# toastershield.net
KiCad netlist of a schematic drawn in EAGLE
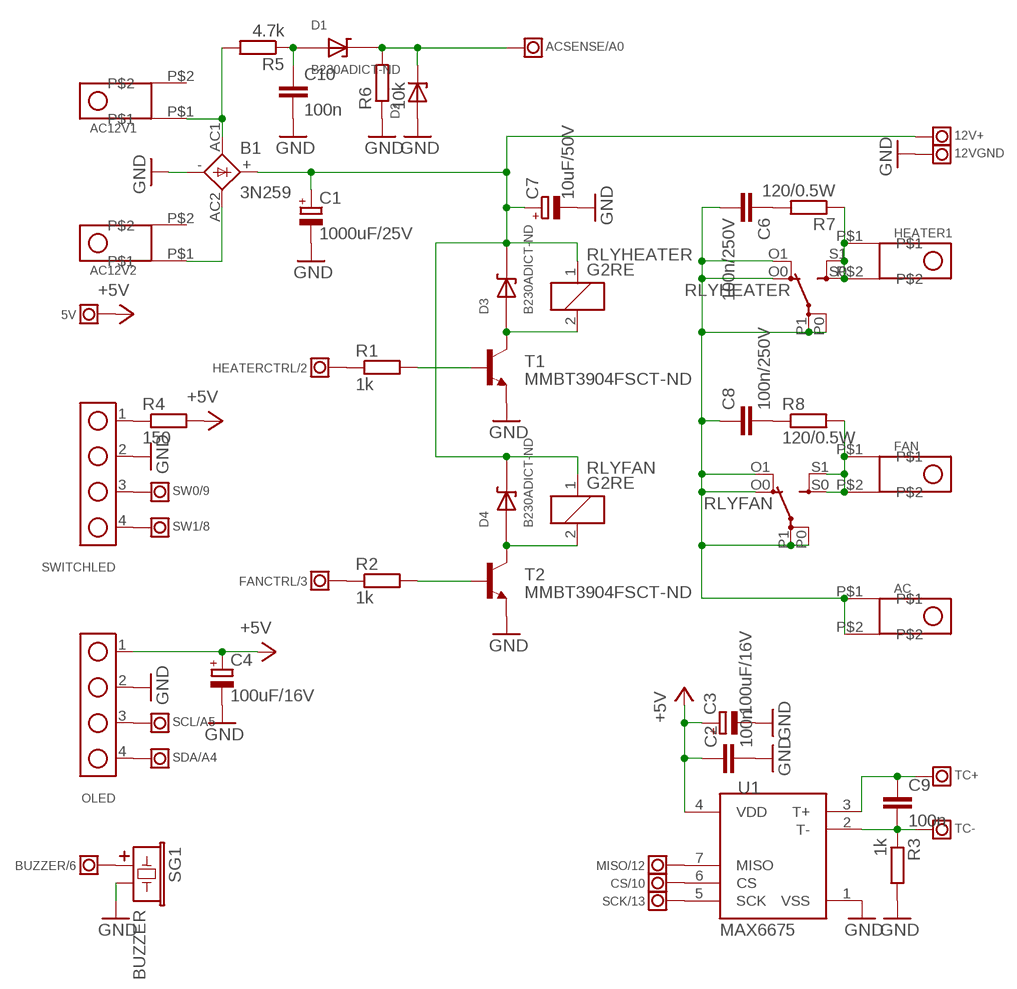
[diagram p0: schematic, sheet 1]

(export (version "E")
  (design (tool "Eeschema 10.0.6"))
  (components
    (comp (ref "5V")
      (value "PIN-HEADER")
      (footprint "eagle-import:PIN-HEADER-MALE")
      (libsource (lib "eagle-import") (part "PIN-HEADER"))
    )
    (comp (ref "12V+")
      (value "PIN-HEADER")
      (footprint "eagle-import:PIN-HEADER-MALE")
      (libsource (lib "eagle-import") (part "PIN-HEADER"))
    )
    (comp (ref "12VGND")
      (value "PIN-HEADER")
      (footprint "eagle-import:PIN-HEADER-MALE")
      (libsource (lib "eagle-import") (part "PIN-HEADER"))
    )
    (comp (ref "AC")
      (value "QUICKCONNECT-TAB")
      (footprint "eagle-import:QUICKCONNECT-TAB-6.35X0.81")
      (libsource (lib "eagle-import") (part "QUICKCONNECT-TAB"))
    )
    (comp (ref "AC12V1")
      (value "QUICKCONNECT-TAB")
      (footprint "eagle-import:QUICKCONNECT-TAB-6.35X0.81")
      (libsource (lib "eagle-import") (part "QUICKCONNECT-TAB"))
    )
    (comp (ref "AC12V2")
      (value "QUICKCONNECT-TAB")
      (footprint "eagle-import:QUICKCONNECT-TAB-6.35X0.81")
      (libsource (lib "eagle-import") (part "QUICKCONNECT-TAB"))
    )
    (comp (ref "ACSENSE/A0")
      (value "PIN-HEADER")
      (footprint "eagle-import:PIN-HEADER-MALE")
      (libsource (lib "eagle-import") (part "PIN-HEADER"))
    )
    (comp (ref "B1")
      (value "3N259")
      (footprint "eagle-import:KBPM")
      (libsource (lib "eagle-import") (part "3N259"))
    )
    (comp (ref "BUZZER/6")
      (value "PIN-HEADER")
      (footprint "eagle-import:PIN-HEADER-MALE")
      (libsource (lib "eagle-import") (part "PIN-HEADER"))
    )
    (comp (ref "C1")
      (value "1000uF/25V")
      (footprint "eagle-import:E5-13")
      (libsource (lib "eagle-import") (part "CPOL-EUE5-13"))
    )
    (comp (ref "C2")
      (value "100n")
      (footprint "eagle-import:C0603")
      (libsource (lib "eagle-import") (part "C-EUC0603"))
    )
    (comp (ref "C3")
      (value "100uF/16V")
      (footprint "eagle-import:E2,5-7")
      (libsource (lib "eagle-import") (part "CPOL-EUE2.5-7"))
    )
    (comp (ref "C4")
      (value "100uF/16V")
      (footprint "eagle-import:E2,5-7")
      (libsource (lib "eagle-import") (part "CPOL-EUE2.5-7"))
    )
    (comp (ref "C6")
      (value "100n/250V")
      (footprint "eagle-import:C1210")
      (libsource (lib "eagle-import") (part "C-EUC1210"))
    )
    (comp (ref "C7")
      (value "10uF/50V")
      (footprint "eagle-import:E2,5-5")
      (libsource (lib "eagle-import") (part "CPOL-EUE2.5-5"))
    )
    (comp (ref "C8")
      (value "100n/250V")
      (footprint "eagle-import:C1210")
      (libsource (lib "eagle-import") (part "C-EUC1210"))
    )
    (comp (ref "C9")
      (value "100n")
      (footprint "eagle-import:C0603")
      (libsource (lib "eagle-import") (part "C-EUC0603"))
    )
    (comp (ref "C10")
      (value "100n")
      (footprint "eagle-import:C0603")
      (libsource (lib "eagle-import") (part "C-EUC0603"))
    )
    (comp (ref "CS/10")
      (value "PIN-HEADER")
      (footprint "eagle-import:PIN-HEADER-MALE")
      (libsource (lib "eagle-import") (part "PIN-HEADER"))
    )
    (comp (ref "D1")
      (value "B230ADICT-ND")
      (footprint "eagle-import:SMA_SMB")
      (libsource (lib "eagle-import") (part "B230ADICT-ND"))
    )
    (comp (ref "D2")
      (value "MA8051CT")
      (footprint "eagle-import:SOD323-W")
      (libsource (lib "eagle-import") (part "MA8051CT"))
    )
    (comp (ref "D3")
      (value "B230ADICT-ND")
      (footprint "eagle-import:SMA_SMB")
      (libsource (lib "eagle-import") (part "B230ADICT-ND"))
    )
    (comp (ref "D4")
      (value "B230ADICT-ND")
      (footprint "eagle-import:SMA_SMB")
      (libsource (lib "eagle-import") (part "B230ADICT-ND"))
    )
    (comp (ref "FAN")
      (value "QUICKCONNECT-TAB")
      (footprint "eagle-import:QUICKCONNECT-TAB-6.35X0.81")
      (libsource (lib "eagle-import") (part "QUICKCONNECT-TAB"))
    )
    (comp (ref "FANCTRL/3")
      (value "PIN-HEADER")
      (footprint "eagle-import:PIN-HEADER-MALE")
      (libsource (lib "eagle-import") (part "PIN-HEADER"))
    )
    (comp (ref "HEATER1")
      (value "QUICKCONNECT-TAB")
      (footprint "eagle-import:QUICKCONNECT-TAB-6.35X0.81")
      (libsource (lib "eagle-import") (part "QUICKCONNECT-TAB"))
    )
    (comp (ref "HEATERCTRL/2")
      (value "PIN-HEADER")
      (footprint "eagle-import:PIN-HEADER-MALE")
      (libsource (lib "eagle-import") (part "PIN-HEADER"))
    )
    (comp (ref "MISO/12")
      (value "PIN-HEADER")
      (footprint "eagle-import:PIN-HEADER-MALE")
      (libsource (lib "eagle-import") (part "PIN-HEADER"))
    )
    (comp (ref "OLED")
      (value "4-PIN-WAFER-CONN")
      (footprint "eagle-import:WAFER_MALE_4PIN")
      (libsource (lib "eagle-import") (part "4-PIN-WAFER-CONN"))
    )
    (comp (ref "R1")
      (value "1k")
      (footprint "eagle-import:R0603")
      (libsource (lib "eagle-import") (part "R-EU_R0603"))
    )
    (comp (ref "R2")
      (value "1k")
      (footprint "eagle-import:R0603")
      (libsource (lib "eagle-import") (part "R-EU_R0603"))
    )
    (comp (ref "R3")
      (value "1k")
      (footprint "eagle-import:R0603")
      (libsource (lib "eagle-import") (part "R-EU_R0603"))
    )
    (comp (ref "R4")
      (value "150")
      (footprint "eagle-import:R0603")
      (libsource (lib "eagle-import") (part "R-EU_R0603"))
    )
    (comp (ref "R5")
      (value "4.7k")
      (footprint "eagle-import:R0603")
      (libsource (lib "eagle-import") (part "R-EU_R0603"))
    )
    (comp (ref "R6")
      (value "10k")
      (footprint "eagle-import:R0603")
      (libsource (lib "eagle-import") (part "R-EU_R0603"))
    )
    (comp (ref "R7")
      (value "120/0.5W")
      (footprint "eagle-import:R1210")
      (libsource (lib "eagle-import") (part "R-EU_R1210"))
    )
    (comp (ref "R8")
      (value "120/0.5W")
      (footprint "eagle-import:R1210")
      (libsource (lib "eagle-import") (part "R-EU_R1210"))
    )
    (comp (ref "RLYFAN")
      (value "G2RE")
      (footprint "eagle-import:G2RE")
      (libsource (lib "eagle-import") (part "G2RE"))
    )
    (comp (ref "RLYHEATER")
      (value "G2RE")
      (footprint "eagle-import:G2RE")
      (libsource (lib "eagle-import") (part "G2RE"))
    )
    (comp (ref "SCK/13")
      (value "PIN-HEADER")
      (footprint "eagle-import:PIN-HEADER-MALE")
      (libsource (lib "eagle-import") (part "PIN-HEADER"))
    )
    (comp (ref "SCL/A5")
      (value "PIN-HEADER")
      (footprint "eagle-import:PIN-HEADER-MALE")
      (libsource (lib "eagle-import") (part "PIN-HEADER"))
    )
    (comp (ref "SDA/A4")
      (value "PIN-HEADER")
      (footprint "eagle-import:PIN-HEADER-MALE")
      (libsource (lib "eagle-import") (part "PIN-HEADER"))
    )
    (comp (ref "SG1")
      (value "BUZZER")
      (footprint "eagle-import:BUZZER-12X7.5")
      (libsource (lib "eagle-import") (part "BUZZER"))
    )
    (comp (ref "SW0/9")
      (value "PIN-HEADER")
      (footprint "eagle-import:PIN-HEADER-MALE")
      (libsource (lib "eagle-import") (part "PIN-HEADER"))
    )
    (comp (ref "SW1/8")
      (value "PIN-HEADER")
      (footprint "eagle-import:PIN-HEADER-MALE")
      (libsource (lib "eagle-import") (part "PIN-HEADER"))
    )
    (comp (ref "SWITCHLED")
      (value "4-PIN-WAFER-CONN")
      (footprint "eagle-import:WAFER_MALE_4PIN")
      (libsource (lib "eagle-import") (part "4-PIN-WAFER-CONN"))
    )
    (comp (ref "T1")
      (value "MMBT3904FSCT-ND")
      (footprint "eagle-import:SOT-23")
      (libsource (lib "eagle-import") (part "MMBT3904FSCT-ND"))
    )
    (comp (ref "T2")
      (value "MMBT3904FSCT-ND")
      (footprint "eagle-import:SOT-23")
      (libsource (lib "eagle-import") (part "MMBT3904FSCT-ND"))
    )
    (comp (ref "TC+")
      (value "PIN-HEADER")
      (footprint "eagle-import:PIN-HEADER-MALE")
      (libsource (lib "eagle-import") (part "PIN-HEADER"))
    )
    (comp (ref "TC-")
      (value "PIN-HEADER")
      (footprint "eagle-import:PIN-HEADER-MALE")
      (libsource (lib "eagle-import") (part "PIN-HEADER"))
    )
    (comp (ref "U1")
      (value "MAX6675")
      (footprint "eagle-import:SO08-MAX6675")
      (libsource (lib "eagle-import") (part "MAX6675"))
    )
  )
  (nets
    (net (code "1") (name "+5V") (class "Default")
      (node (ref "5V") (pin "P$1") (pinfunction "P$1_P$1") (pintype "bidirectional"))
      (node (ref "C2") (pin "1") (pinfunction "1_1") (pintype "passive"))
      (node (ref "C3") (pin "+") (pinfunction "+_+") (pintype "passive"))
      (node (ref "C4") (pin "+") (pinfunction "+_+") (pintype "passive"))
      (node (ref "OLED") (pin "1") (pinfunction "1_1") (pintype "bidirectional"))
      (node (ref "R4") (pin "2") (pinfunction "2_2") (pintype "passive"))
      (node (ref "U1") (pin "4") (pinfunction "VDD_4") (pintype "bidirectional"))
    )
    (net (code "2") (name "GND") (class "Default")
      (node (ref "12VGND") (pin "P$1") (pinfunction "P$1_P$1") (pintype "bidirectional"))
      (node (ref "B1") (pin "-") (pinfunction "-_-") (pintype "passive"))
      (node (ref "C1") (pin "-") (pinfunction "-_-") (pintype "passive"))
      (node (ref "C10") (pin "2") (pinfunction "2_2") (pintype "passive"))
      (node (ref "C2") (pin "2") (pinfunction "2_2") (pintype "passive"))
      (node (ref "C3") (pin "-") (pinfunction "-_-") (pintype "passive"))
      (node (ref "C4") (pin "-") (pinfunction "-_-") (pintype "passive"))
      (node (ref "C7") (pin "-") (pinfunction "-_-") (pintype "passive"))
      (node (ref "D2") (pin "A") (pinfunction "AN_A") (pintype "bidirectional"))
      (node (ref "OLED") (pin "2") (pinfunction "2_2") (pintype "bidirectional"))
      (node (ref "R3") (pin "2") (pinfunction "2_2") (pintype "passive"))
      (node (ref "R6") (pin "1") (pinfunction "1_1") (pintype "passive"))
      (node (ref "SG1") (pin "-") (pinfunction "2_-") (pintype "passive"))
      (node (ref "SWITCHLED") (pin "2") (pinfunction "2_2") (pintype "bidirectional"))
      (node (ref "T1") (pin "2") (pinfunction "E_2") (pintype "passive"))
      (node (ref "T2") (pin "2") (pinfunction "E_2") (pintype "passive"))
      (node (ref "U1") (pin "1") (pinfunction "VSS_1") (pintype "bidirectional"))
    )
    (net (code "3") (name "Net-(AC-PadP$1)") (class "Default")
      (node (ref "AC") (pin "P$1") (pinfunction "P$1_P$1") (pintype "bidirectional"))
      (node (ref "AC") (pin "P$2") (pinfunction "P$2_P$2") (pintype "bidirectional"))
      (node (ref "C6") (pin "2") (pinfunction "2_2") (pintype "passive"))
      (node (ref "C8") (pin "1") (pinfunction "1_1") (pintype "passive"))
      (node (ref "RLYFAN") (pin "O0") (pinfunction "O_O0") (pintype "passive"))
      (node (ref "RLYFAN") (pin "O1") (pinfunction "O_O1") (pintype "passive"))
      (node (ref "RLYFAN") (pin "P0") (pinfunction "P_P0") (pintype "passive"))
      (node (ref "RLYFAN") (pin "P1") (pinfunction "P_P1") (pintype "passive"))
      (node (ref "RLYHEATER") (pin "O0") (pinfunction "O_O0") (pintype "passive"))
      (node (ref "RLYHEATER") (pin "O1") (pinfunction "O_O1") (pintype "passive"))
      (node (ref "RLYHEATER") (pin "P0") (pinfunction "P_P0") (pintype "passive"))
      (node (ref "RLYHEATER") (pin "P1") (pinfunction "P_P1") (pintype "passive"))
    )
    (net (code "4") (name "Net-(AC12V1-PadP$1)") (class "Default")
      (node (ref "AC12V1") (pin "P$1") (pinfunction "P$1_P$1") (pintype "bidirectional"))
      (node (ref "B1") (pin "AC1") (pinfunction "AC1_AC1") (pintype "passive"))
      (node (ref "R5") (pin "2") (pinfunction "2_2") (pintype "passive"))
    )
    (net (code "5") (name "Net-(AC12V2-PadP$1)") (class "Default")
      (node (ref "AC12V2") (pin "P$1") (pinfunction "P$1_P$1") (pintype "bidirectional"))
      (node (ref "B1") (pin "AC2") (pinfunction "AC2_AC2") (pintype "passive"))
    )
    (net (code "6") (name "Net-(C6-Pad1)") (class "Default")
      (node (ref "C6") (pin "1") (pinfunction "1_1") (pintype "passive"))
      (node (ref "R7") (pin "2") (pinfunction "2_2") (pintype "passive"))
    )
    (net (code "7") (name "Net-(C8-Pad2)") (class "Default")
      (node (ref "C8") (pin "2") (pinfunction "2_2") (pintype "passive"))
      (node (ref "R8") (pin "1") (pinfunction "1_1") (pintype "passive"))
    )
    (net (code "8") (name "Net-(D1-AN)") (class "Default")
      (node (ref "C10") (pin "1") (pinfunction "1_1") (pintype "passive"))
      (node (ref "D1") (pin "2") (pinfunction "AN_2") (pintype "bidirectional"))
      (node (ref "R5") (pin "1") (pinfunction "1_1") (pintype "passive"))
    )
    (net (code "9") (name "Net-(D1-CAT)") (class "Default")
      (node (ref "ACSENSE/A0") (pin "P$1") (pinfunction "P$1_P$1") (pintype "bidirectional"))
      (node (ref "D1") (pin "1") (pinfunction "CAT_1") (pintype "bidirectional"))
      (node (ref "D2") (pin "C") (pinfunction "CAT_C") (pintype "bidirectional"))
      (node (ref "R6") (pin "2") (pinfunction "2_2") (pintype "passive"))
    )
    (net (code "10") (name "Net-(D3-AN)") (class "Default")
      (node (ref "D3") (pin "2") (pinfunction "AN_2") (pintype "bidirectional"))
      (node (ref "RLYHEATER") (pin "2") (pinfunction "2_2") (pintype "passive"))
      (node (ref "T1") (pin "3") (pinfunction "C_3") (pintype "passive"))
    )
    (net (code "11") (name "Net-(D3-CAT)") (class "Default")
      (node (ref "12V+") (pin "P$1") (pinfunction "P$1_P$1") (pintype "bidirectional"))
      (node (ref "B1") (pin "+") (pinfunction "+_+") (pintype "passive"))
      (node (ref "C1") (pin "+") (pinfunction "+_+") (pintype "passive"))
      (node (ref "C7") (pin "+") (pinfunction "+_+") (pintype "passive"))
      (node (ref "D3") (pin "1") (pinfunction "CAT_1") (pintype "bidirectional"))
      (node (ref "D4") (pin "1") (pinfunction "CAT_1") (pintype "bidirectional"))
      (node (ref "RLYFAN") (pin "1") (pinfunction "1_1") (pintype "passive"))
      (node (ref "RLYHEATER") (pin "1") (pinfunction "1_1") (pintype "passive"))
    )
    (net (code "12") (name "Net-(D4-AN)") (class "Default")
      (node (ref "D4") (pin "2") (pinfunction "AN_2") (pintype "bidirectional"))
      (node (ref "RLYFAN") (pin "2") (pinfunction "2_2") (pintype "passive"))
      (node (ref "T2") (pin "3") (pinfunction "C_3") (pintype "passive"))
    )
    (net (code "13") (name "Net-(FAN-PadP$1)") (class "Default")
      (node (ref "FAN") (pin "P$1") (pinfunction "P$1_P$1") (pintype "bidirectional"))
      (node (ref "FAN") (pin "P$2") (pinfunction "P$2_P$2") (pintype "bidirectional"))
      (node (ref "R8") (pin "2") (pinfunction "2_2") (pintype "passive"))
      (node (ref "RLYFAN") (pin "S0") (pinfunction "S_S0") (pintype "passive"))
      (node (ref "RLYFAN") (pin "S1") (pinfunction "S_S1") (pintype "passive"))
    )
    (net (code "14") (name "Net-(FANCTRL/3-PadP$1)") (class "Default")
      (node (ref "FANCTRL/3") (pin "P$1") (pinfunction "P$1_P$1") (pintype "bidirectional"))
      (node (ref "R2") (pin "1") (pinfunction "1_1") (pintype "passive"))
    )
    (net (code "15") (name "Net-(HEATER1-PadP$1)") (class "Default")
      (node (ref "HEATER1") (pin "P$1") (pinfunction "P$1_P$1") (pintype "bidirectional"))
      (node (ref "HEATER1") (pin "P$2") (pinfunction "P$2_P$2") (pintype "bidirectional"))
      (node (ref "R7") (pin "1") (pinfunction "1_1") (pintype "passive"))
      (node (ref "RLYHEATER") (pin "S0") (pinfunction "S_S0") (pintype "passive"))
      (node (ref "RLYHEATER") (pin "S1") (pinfunction "S_S1") (pintype "passive"))
    )
    (net (code "16") (name "Net-(HEATERCTRL/2-PadP$1)") (class "Default")
      (node (ref "HEATERCTRL/2") (pin "P$1") (pinfunction "P$1_P$1") (pintype "bidirectional"))
      (node (ref "R1") (pin "1") (pinfunction "1_1") (pintype "passive"))
    )
    (net (code "17") (name "Net-(OLED-Pad3)") (class "Default")
      (node (ref "OLED") (pin "3") (pinfunction "3_3") (pintype "bidirectional"))
      (node (ref "SCL/A5") (pin "P$1") (pinfunction "P$1_P$1") (pintype "bidirectional"))
    )
    (net (code "18") (name "Net-(OLED-Pad4)") (class "Default")
      (node (ref "OLED") (pin "4") (pinfunction "4_4") (pintype "bidirectional"))
      (node (ref "SDA/A4") (pin "P$1") (pinfunction "P$1_P$1") (pintype "bidirectional"))
    )
    (net (code "19") (name "Net-(R4-Pad1)") (class "Default")
      (node (ref "R4") (pin "1") (pinfunction "1_1") (pintype "passive"))
      (node (ref "SWITCHLED") (pin "1") (pinfunction "1_1") (pintype "bidirectional"))
    )
    (net (code "20") (name "Net-(SG1-1)") (class "Default")
      (node (ref "BUZZER/6") (pin "P$1") (pinfunction "P$1_P$1") (pintype "bidirectional"))
      (node (ref "SG1") (pin "+") (pinfunction "1_+") (pintype "passive"))
    )
    (net (code "21") (name "Net-(SW0/9-PadP$1)") (class "Default")
      (node (ref "SW0/9") (pin "P$1") (pinfunction "P$1_P$1") (pintype "bidirectional"))
      (node (ref "SWITCHLED") (pin "3") (pinfunction "3_3") (pintype "bidirectional"))
    )
    (net (code "22") (name "Net-(SW1/8-PadP$1)") (class "Default")
      (node (ref "SW1/8") (pin "P$1") (pinfunction "P$1_P$1") (pintype "bidirectional"))
      (node (ref "SWITCHLED") (pin "4") (pinfunction "4_4") (pintype "bidirectional"))
    )
    (net (code "23") (name "Net-(T1-B)") (class "Default")
      (node (ref "R1") (pin "2") (pinfunction "2_2") (pintype "passive"))
      (node (ref "T1") (pin "1") (pinfunction "B_1") (pintype "passive"))
    )
    (net (code "24") (name "Net-(T2-B)") (class "Default")
      (node (ref "R2") (pin "2") (pinfunction "2_2") (pintype "passive"))
      (node (ref "T2") (pin "1") (pinfunction "B_1") (pintype "passive"))
    )
    (net (code "25") (name "Net-(U1-CS)") (class "Default")
      (node (ref "CS/10") (pin "P$1") (pinfunction "P$1_P$1") (pintype "bidirectional"))
      (node (ref "U1") (pin "6") (pinfunction "CS_6") (pintype "bidirectional"))
    )
    (net (code "26") (name "Net-(U1-MISO)") (class "Default")
      (node (ref "MISO/12") (pin "P$1") (pinfunction "P$1_P$1") (pintype "bidirectional"))
      (node (ref "U1") (pin "7") (pinfunction "MISO_7") (pintype "bidirectional"))
    )
    (net (code "27") (name "Net-(U1-SCK)") (class "Default")
      (node (ref "SCK/13") (pin "P$1") (pinfunction "P$1_P$1") (pintype "bidirectional"))
      (node (ref "U1") (pin "5") (pinfunction "SCK_5") (pintype "bidirectional"))
    )
    (net (code "28") (name "Net-(U1-T+)") (class "Default")
      (node (ref "C9") (pin "1") (pinfunction "1_1") (pintype "passive"))
      (node (ref "TC+") (pin "P$1") (pinfunction "P$1_P$1") (pintype "bidirectional"))
      (node (ref "U1") (pin "3") (pinfunction "T+_3") (pintype "bidirectional"))
    )
    (net (code "29") (name "Net-(U1-T-)") (class "Default")
      (node (ref "C9") (pin "2") (pinfunction "2_2") (pintype "passive"))
      (node (ref "R3") (pin "1") (pinfunction "1_1") (pintype "passive"))
      (node (ref "TC-") (pin "P$1") (pinfunction "P$1_P$1") (pintype "bidirectional"))
      (node (ref "U1") (pin "2") (pinfunction "T-_2") (pintype "bidirectional"))
    )
    (net (code "30") (name "unconnected-(AC12V1-PadP$2)") (class "Default")
      (node (ref "AC12V1") (pin "P$2") (pinfunction "P$2_P$2") (pintype "bidirectional"))
    )
    (net (code "31") (name "unconnected-(AC12V2-PadP$2)") (class "Default")
      (node (ref "AC12V2") (pin "P$2") (pinfunction "P$2_P$2") (pintype "bidirectional"))
    )
  )
)
